# EAA690_RFID_In.net
KiCad netlist of a schematic drawn in EAGLE
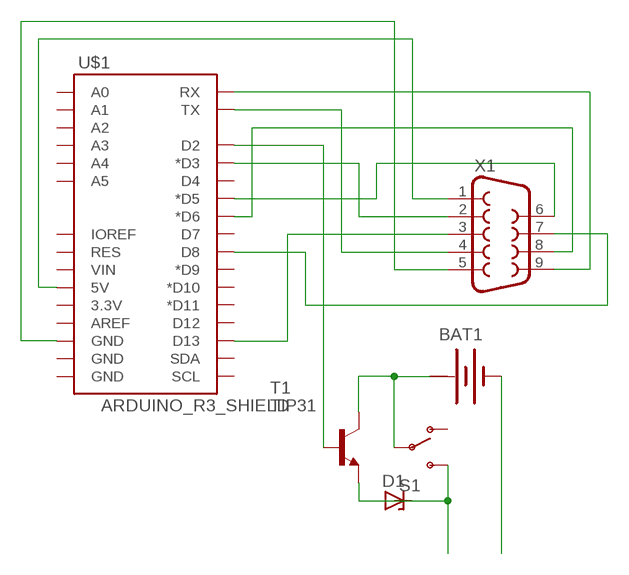
[diagram p0: schematic, sheet 1]

(export (version "E")
  (design (tool "Eeschema 10.0.6"))
  (components
    (comp (ref "BAT1")
      (value "BATTERY")
      (footprint "eagle-import:BATTERY")
      (libsource (lib "eagle-import") (part "BATTERY"))
    )
    (comp (ref "D1")
      (value "ZENER-DIODESOD64-12")
      (footprint "eagle-import:SOD64Z12")
      (libsource (lib "eagle-import") (part "ZENER-DIODESOD64-12"))
    )
    (comp (ref "S1")
      (value "SWITCH-SPDTPTH")
      (footprint "eagle-import:SWITCH-SPDT")
      (libsource (lib "eagle-import") (part "SWITCH-SPDTPTH"))
    )
    (comp (ref "T1")
      (value "TIP31")
      (footprint "eagle-import:TO220")
      (libsource (lib "eagle-import") (part "TIP31"))
    )
    (comp (ref "U$1")
      (value "ARDUINO_R3_SHIELD")
      (footprint "eagle-import:UNO_R3_SHIELD")
      (libsource (lib "eagle-import") (part "ARDUINO_R3_SHIELD"))
    )
    (comp (ref "X1")
      (value "DB9FEMALE")
      (footprint "eagle-import:DB9")
      (libsource (lib "eagle-import") (part "DB9FEMALE"))
    )
  )
  (nets
    (net (code "1") (name "/+") (class "Default")
      (node (ref "BAT1") (pin "+@1") (pinfunction "+_+@1") (pintype "power_in"))
    )
    (net (code "2") (name "Net-(S1-P)") (class "Default")
      (node (ref "BAT1") (pin "+") (pinfunction "+_+") (pintype "power_in"))
      (node (ref "S1") (pin "2") (pinfunction "P_2") (pintype "passive"))
      (node (ref "T1") (pin "2") (pinfunction "C_2") (pintype "passive"))
    )
    (net (code "3") (name "Net-(S1-S)") (class "Default")
      (node (ref "D1") (pin "A") (pinfunction "A_A") (pintype "passive"))
      (node (ref "D1") (pin "C") (pinfunction "C_C") (pintype "passive"))
      (node (ref "S1") (pin "3") (pinfunction "S_3") (pintype "passive"))
      (node (ref "T1") (pin "3") (pinfunction "E_3") (pintype "passive"))
    )
    (net (code "4") (name "Net-(T1-B)") (class "Default")
      (node (ref "T1") (pin "1") (pinfunction "B_1") (pintype "passive"))
      (node (ref "U$1") (pin "D2") (pinfunction "D2_D2") (pintype "bidirectional"))
    )
    (net (code "5") (name "Net-(U$1-*D3)") (class "Default")
      (node (ref "U$1") (pin "D3") (pinfunction "*D3_D3") (pintype "bidirectional"))
      (node (ref "X1") (pin "2") (pinfunction "2_2") (pintype "passive"))
    )
    (net (code "6") (name "Net-(U$1-*D5)") (class "Default")
      (node (ref "U$1") (pin "D5") (pinfunction "*D5_D5") (pintype "bidirectional"))
      (node (ref "X1") (pin "6") (pinfunction "6_6") (pintype "passive"))
    )
    (net (code "7") (name "Net-(U$1-*D6)") (class "Default")
      (node (ref "U$1") (pin "D6") (pinfunction "*D6_D6") (pintype "bidirectional"))
      (node (ref "X1") (pin "8") (pinfunction "8_8") (pintype "passive"))
    )
    (net (code "8") (name "Net-(U$1-GND-PadGND@2)") (class "Default")
      (node (ref "U$1") (pin "GND@2") (pinfunction "GND_GND@2") (pintype "bidirectional"))
      (node (ref "X1") (pin "5") (pinfunction "5_5") (pintype "passive"))
    )
    (net (code "9") (name "Net-(U$1-Pad5V)") (class "Default")
      (node (ref "U$1") (pin "5V") (pinfunction "5V_5V") (pintype "bidirectional"))
      (node (ref "X1") (pin "1") (pinfunction "1_1") (pintype "passive"))
    )
    (net (code "10") (name "Net-(U$1-PadD8)") (class "Default")
      (node (ref "U$1") (pin "D8") (pinfunction "D8_D8") (pintype "bidirectional"))
      (node (ref "X1") (pin "7") (pinfunction "7_7") (pintype "passive"))
    )
    (net (code "11") (name "Net-(U$1-PadD13)") (class "Default")
      (node (ref "U$1") (pin "D13") (pinfunction "D13_D13") (pintype "bidirectional"))
      (node (ref "X1") (pin "3") (pinfunction "3_3") (pintype "passive"))
    )
    (net (code "12") (name "Net-(U$1-PadRX)") (class "Default")
      (node (ref "U$1") (pin "RX") (pinfunction "RX_RX") (pintype "bidirectional"))
      (node (ref "X1") (pin "9") (pinfunction "9_9") (pintype "passive"))
    )
    (net (code "13") (name "Net-(U$1-PadTX)") (class "Default")
      (node (ref "U$1") (pin "TX") (pinfunction "TX_TX") (pintype "bidirectional"))
      (node (ref "X1") (pin "4") (pinfunction "4_4") (pintype "passive"))
    )
    (net (code "14") (name "unconnected-(BAT1-Pad-)") (class "Default")
      (node (ref "BAT1") (pin "-") (pinfunction "-_-") (pintype "power_in"))
    )
    (net (code "15") (name "unconnected-(S1-O-Pad1)") (class "Default")
      (node (ref "S1") (pin "1") (pinfunction "O_1") (pintype "passive"))
    )
    (net (code "16") (name "unconnected-(U$1-*D9-PadD9)") (class "Default")
      (node (ref "U$1") (pin "D9") (pinfunction "*D9_D9") (pintype "bidirectional"))
    )
    (net (code "17") (name "unconnected-(U$1-*D10-PadD10)") (class "Default")
      (node (ref "U$1") (pin "D10") (pinfunction "*D10_D10") (pintype "bidirectional"))
    )
    (net (code "18") (name "unconnected-(U$1-*D11-PadD11)") (class "Default")
      (node (ref "U$1") (pin "D11") (pinfunction "*D11_D11") (pintype "bidirectional"))
    )
    (net (code "19") (name "unconnected-(U$1-GND-PadGND@0)") (class "Default")
      (node (ref "U$1") (pin "GND@0") (pinfunction "GND_GND@0") (pintype "bidirectional"))
    )
    (net (code "20") (name "unconnected-(U$1-GND-PadGND@1)") (class "Default")
      (node (ref "U$1") (pin "GND@1") (pinfunction "GND_GND@1") (pintype "bidirectional"))
    )
    (net (code "21") (name "unconnected-(U$1-Pad3.3V)") (class "Default")
      (node (ref "U$1") (pin "3.3V") (pinfunction "3.3V_3.3V") (pintype "bidirectional"))
    )
    (net (code "22") (name "unconnected-(U$1-PadA0)") (class "Default")
      (node (ref "U$1") (pin "A0") (pinfunction "A0_A0") (pintype "bidirectional"))
    )
    (net (code "23") (name "unconnected-(U$1-PadA1)") (class "Default")
      (node (ref "U$1") (pin "A1") (pinfunction "A1_A1") (pintype "bidirectional"))
    )
    (net (code "24") (name "unconnected-(U$1-PadA2)") (class "Default")
      (node (ref "U$1") (pin "A2") (pinfunction "A2_A2") (pintype "bidirectional"))
    )
    (net (code "25") (name "unconnected-(U$1-PadA3)") (class "Default")
      (node (ref "U$1") (pin "A3") (pinfunction "A3_A3") (pintype "bidirectional"))
    )
    (net (code "26") (name "unconnected-(U$1-PadA4)") (class "Default")
      (node (ref "U$1") (pin "A4") (pinfunction "A4_A4") (pintype "bidirectional"))
    )
    (net (code "27") (name "unconnected-(U$1-PadA5)") (class "Default")
      (node (ref "U$1") (pin "A5") (pinfunction "A5_A5") (pintype "bidirectional"))
    )
    (net (code "28") (name "unconnected-(U$1-PadAREF)") (class "Default")
      (node (ref "U$1") (pin "AREF") (pinfunction "AREF_AREF") (pintype "bidirectional"))
    )
    (net (code "29") (name "unconnected-(U$1-PadD4)") (class "Default")
      (node (ref "U$1") (pin "D4") (pinfunction "D4_D4") (pintype "bidirectional"))
    )
    (net (code "30") (name "unconnected-(U$1-PadD7)") (class "Default")
      (node (ref "U$1") (pin "D7") (pinfunction "D7_D7") (pintype "bidirectional"))
    )
    (net (code "31") (name "unconnected-(U$1-PadD12)") (class "Default")
      (node (ref "U$1") (pin "D12") (pinfunction "D12_D12") (pintype "bidirectional"))
    )
    (net (code "32") (name "unconnected-(U$1-PadIOREF)") (class "Default")
      (node (ref "U$1") (pin "IOREF") (pinfunction "IOREF_IOREF") (pintype "bidirectional"))
    )
    (net (code "33") (name "unconnected-(U$1-PadRES)") (class "Default")
      (node (ref "U$1") (pin "RES") (pinfunction "RES_RES") (pintype "bidirectional"))
    )
    (net (code "34") (name "unconnected-(U$1-PadSCL)") (class "Default")
      (node (ref "U$1") (pin "SCL") (pinfunction "SCL_SCL") (pintype "bidirectional"))
    )
    (net (code "35") (name "unconnected-(U$1-PadSDA)") (class "Default")
      (node (ref "U$1") (pin "SDA") (pinfunction "SDA_SDA") (pintype "bidirectional"))
    )
    (net (code "36") (name "unconnected-(U$1-PadVIN)") (class "Default")
      (node (ref "U$1") (pin "VIN") (pinfunction "VIN_VIN") (pintype "bidirectional"))
    )
  )
)
